# 04-ORIN_HIGH_SPEED_SIGNAL_2.net
KiCad netlist of a schematic drawn in Altium Designer
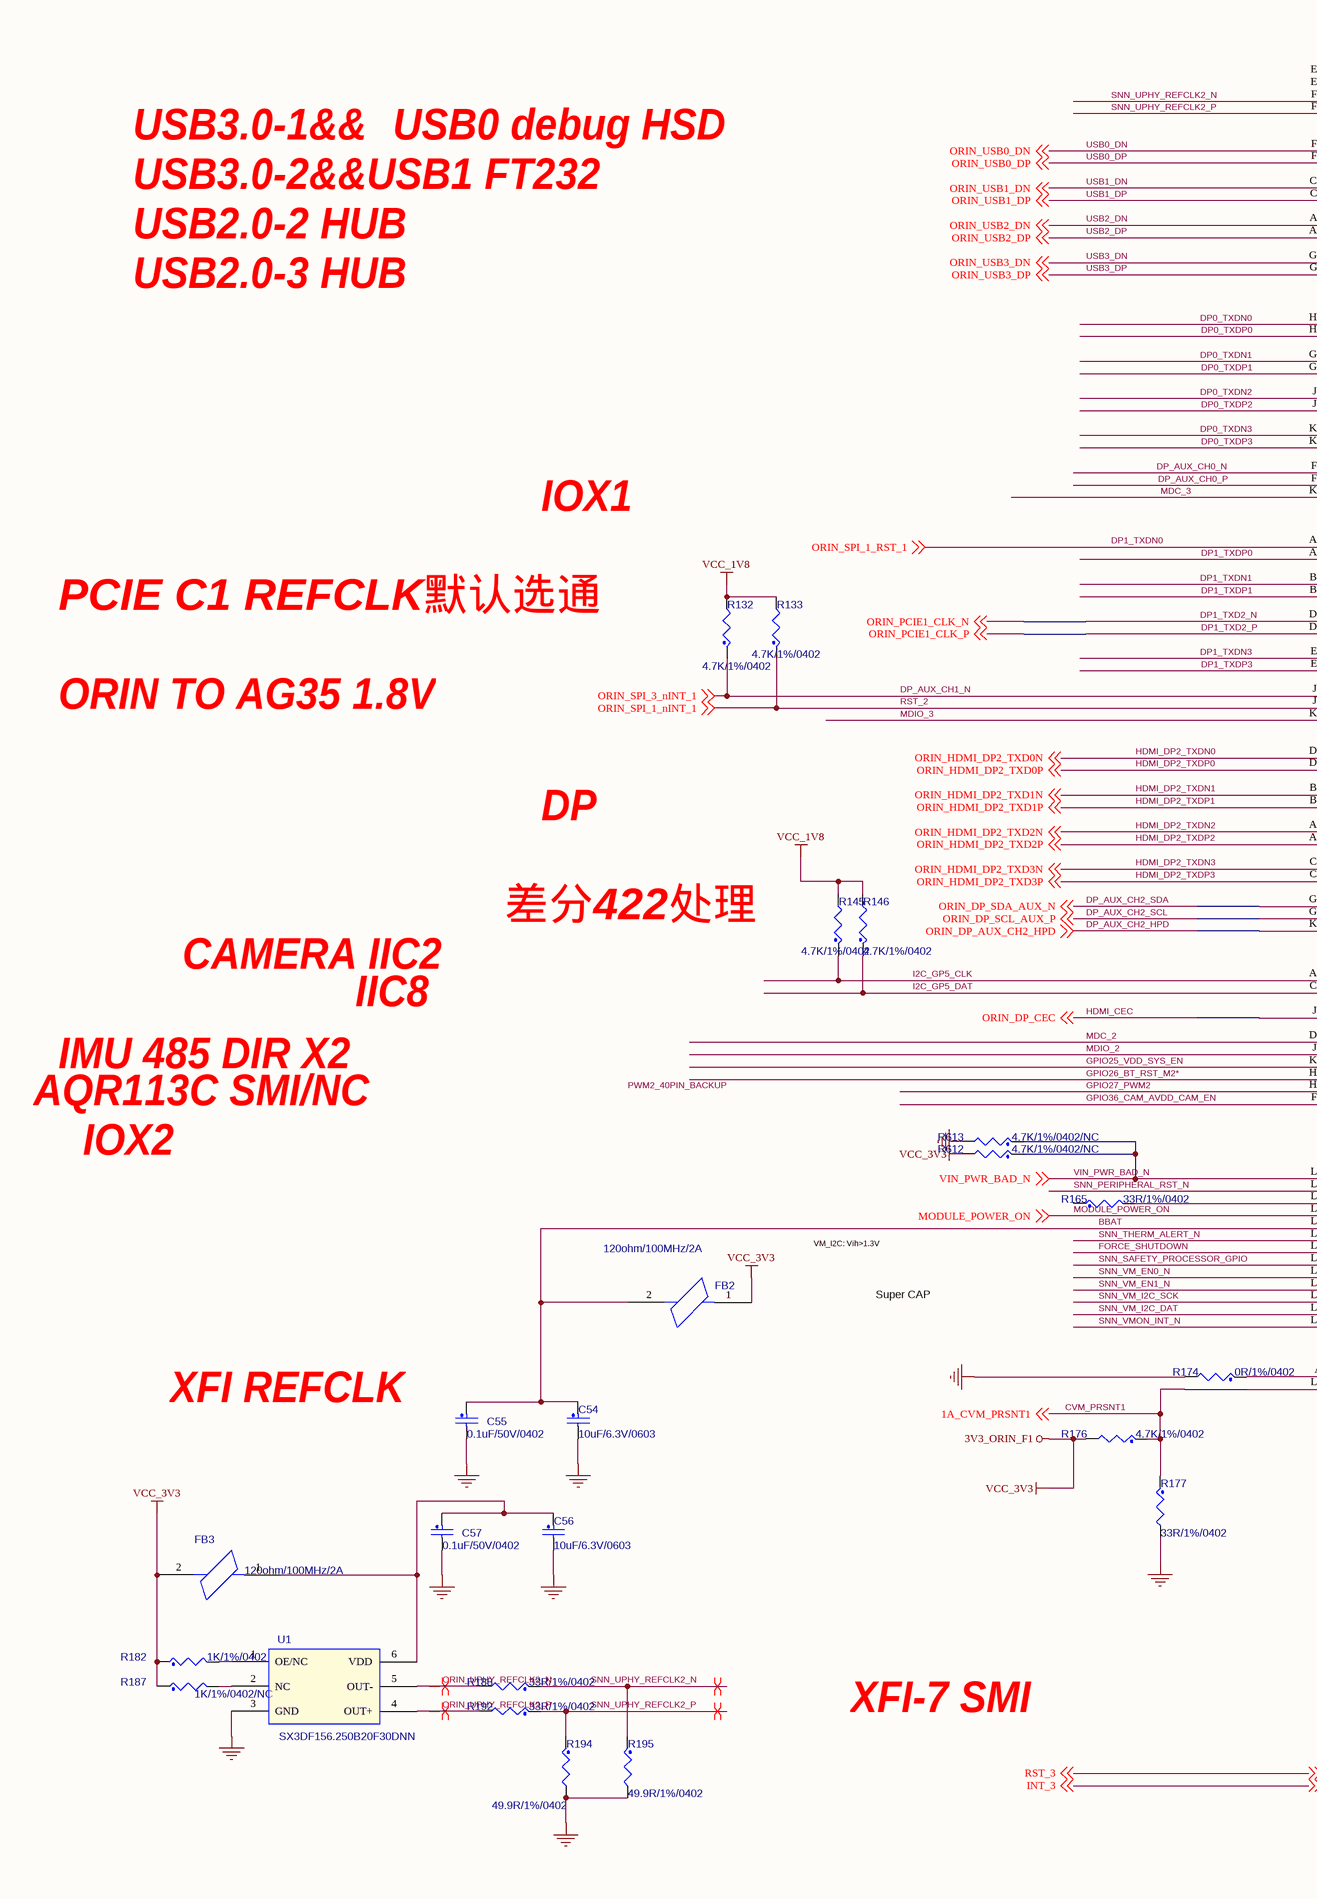
[diagram p0: 04-ORIN_HIGH_SPEED_SIGNAL_2.SchDoc, left]
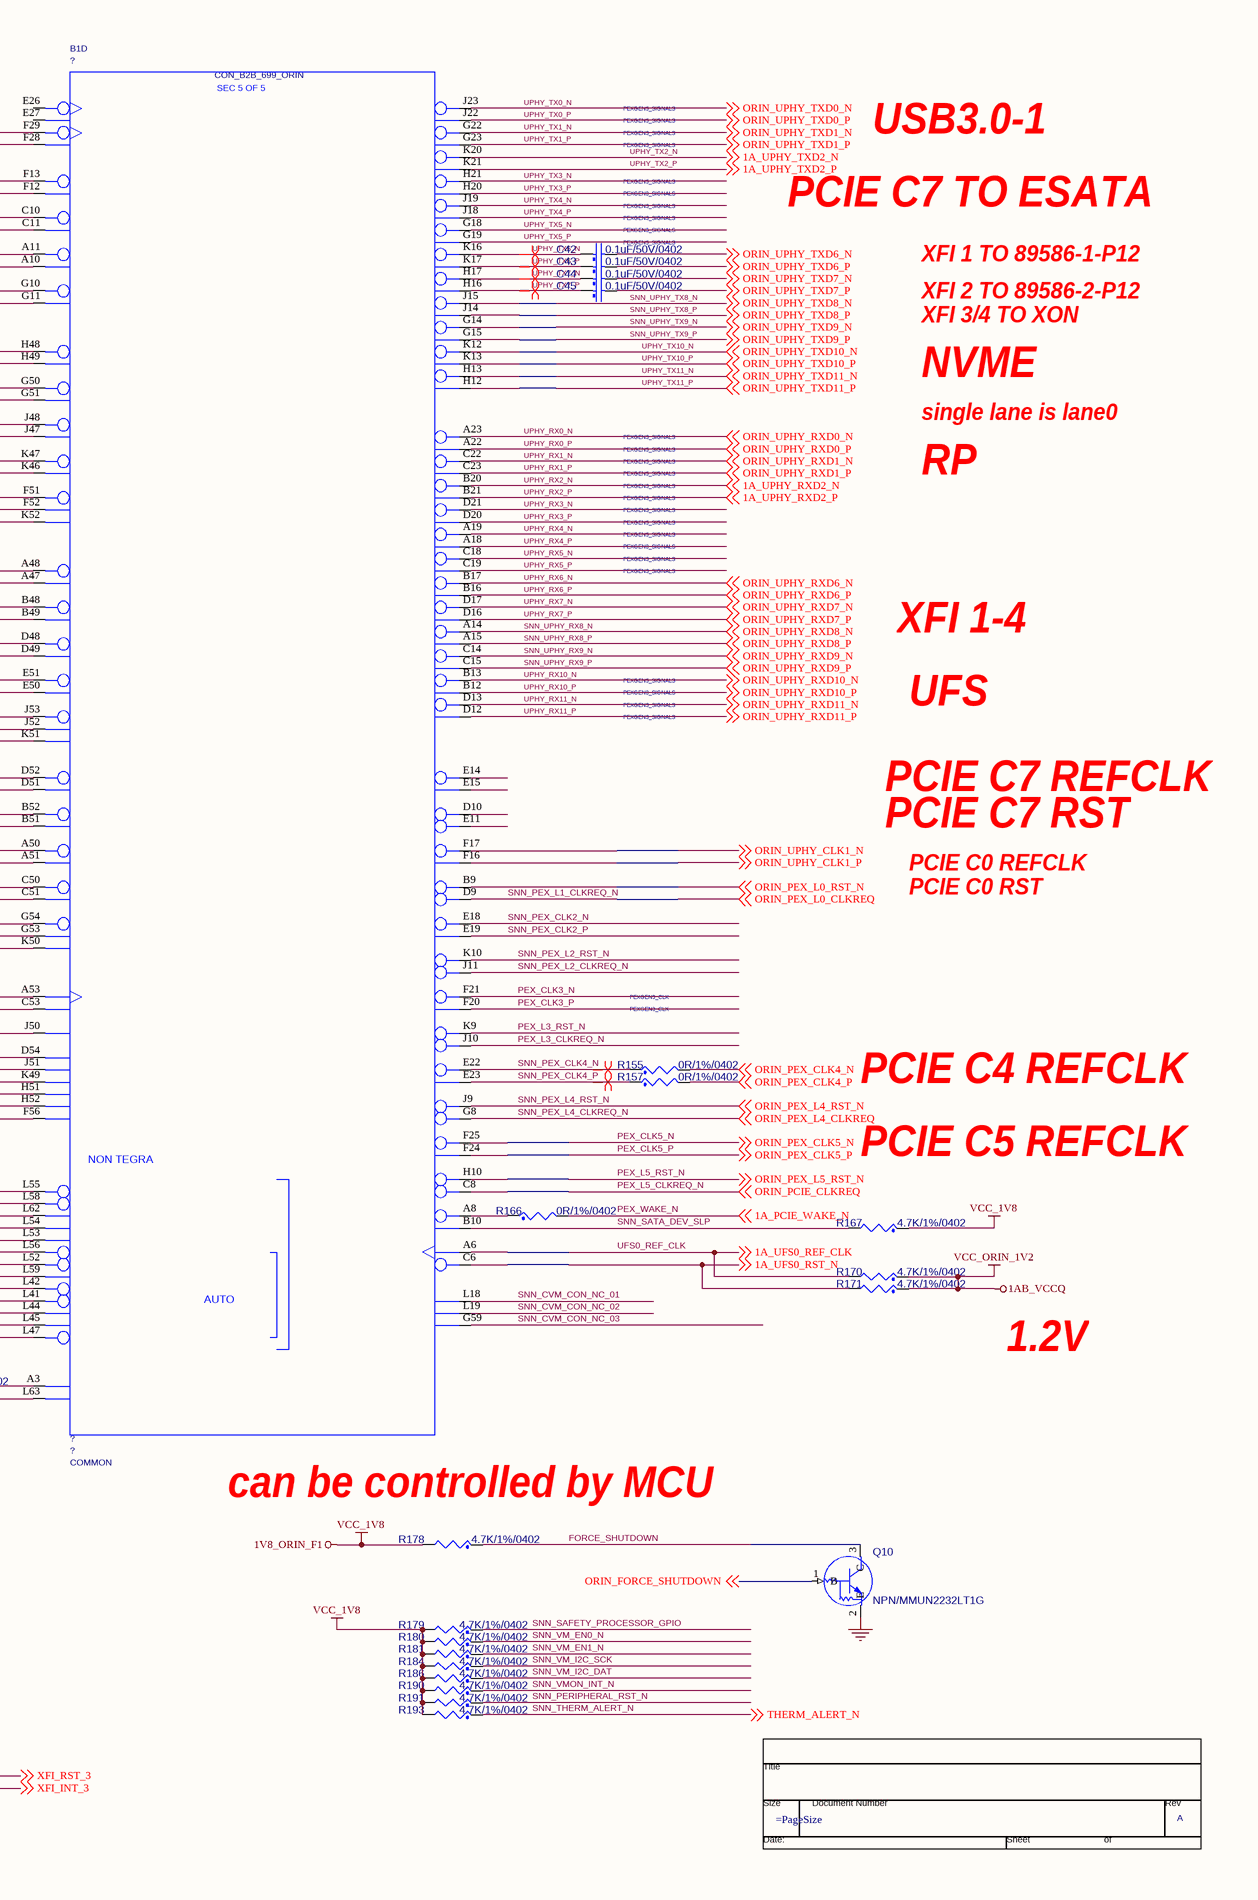
[diagram p1: 04-ORIN_HIGH_SPEED_SIGNAL_2.SchDoc, right]

(export (version "E")
  (design (tool "Eeschema 10.0.6"))
  (components
    (comp (ref "B1")
      (value "CON_B2B_699_ORIN")
      (footprint "CON_MIRMEZ_699_BGA_ST_P009_P013_P015_REVERSE")
      (description "2034560003/MOLEX")
      (fields
        (field (name "DEVICE") "CON_B2B_699_ORIN")
        (field (name "NV_PN") "?")
        (field (name "PACK_TYPE") "?")
        (field (name "PATH") "?")
        (field (name "SKU") "COMMON")
      )
      (libsource (lib "*") (part "CON_B2B_699"))
    )
    (comp (ref "C42")
      (value "0.1uF/50V/0402")
      (footprint "C0402")
      (description "GCM155R71H104KE02/MURATA")
      (fields (field (name "TOLERANCE") "10%") (field (name "VOLTAGE") "16V"))
      (libsource (lib "*") (part "CAP_NP"))
    )
    (comp (ref "C43")
      (value "0.1uF/50V/0402")
      (footprint "C0402")
      (description "GCM155R71H104KE02/MURATA")
      (fields (field (name "TOLERANCE") "10%") (field (name "VOLTAGE") "16V"))
      (libsource (lib "*") (part "CAP_NP"))
    )
    (comp (ref "C44")
      (value "0.1uF/50V/0402")
      (footprint "C0402")
      (description "GCM155R71H104KE02/MURATA")
      (fields (field (name "TOLERANCE") "10%") (field (name "VOLTAGE") "16V"))
      (libsource (lib "*") (part "CAP_NP"))
    )
    (comp (ref "C45")
      (value "0.1uF/50V/0402")
      (footprint "C0402")
      (description "GCM155R71H104KE02/MURATA")
      (fields (field (name "TOLERANCE") "10%") (field (name "VOLTAGE") "16V"))
      (libsource (lib "*") (part "CAP_NP"))
    )
    (comp (ref "C54")
      (value "10uF/6.3V/0603")
      (footprint "C0603")
      (description "GCM188D70J106ME36/MURATA")
      (fields (field (name "VOLTAGE") "10v") (field (name "TOLERANCE") "10%"))
      (libsource (lib "*") (part "CAP_NP"))
    )
    (comp (ref "C55")
      (value "0.1uF/50V/0402")
      (footprint "C0402")
      (description "GCM155R71H104KE02/MURATA")
      (fields (field (name "TOLERANCE") "10%") (field (name "VOLTAGE") "16V"))
      (libsource (lib "*") (part "CAP_NP"))
    )
    (comp (ref "C56")
      (value "10uF/6.3V/0603")
      (footprint "C0603")
      (description "GCM188D70J106ME36/MURATA")
      (fields (field (name "VOLTAGE") "10v") (field (name "TOLERANCE") "10%"))
      (libsource (lib "*") (part "CAP_NP"))
    )
    (comp (ref "C57")
      (value "0.1uF/50V/0402")
      (footprint "C0402")
      (description "GCM155R71H104KE02/MURATA")
      (fields (field (name "TOLERANCE") "10%") (field (name "VOLTAGE") "16V"))
      (libsource (lib "*") (part "CAP_NP"))
    )
    (comp (ref "FB2")
      (value "120ohm/100MHz/2A")
      (footprint "L0603")
      (description "BLM18EG121SH1D/MURATA")
      (fields (field (name "Comment") "BEAD_FERRITE"))
      (libsource (lib "*") (part "BEAD_FERRITE"))
    )
    (comp (ref "FB3")
      (value "120ohm/100MHz/2A")
      (footprint "L0603")
      (description "BLM18EG121SH1D/MURATA")
      (fields (field (name "Comment") "BEAD_FERRITE"))
      (libsource (lib "*") (part "BEAD_FERRITE"))
    )
    (comp (ref "Q10")
      (value "NPN/MMUN2232LT1G")
      (footprint "SOT-23")
      (description "MMUN2232LT1G/ONSEMI")
      (libsource (lib "*") (part "DTC143ZE"))
    )
    (comp (ref "R132")
      (value "4.7K/1%/0402")
      (footprint "R0402")
      (description "AC0402FR-074K7L/YAGEO")
      (fields (field (name "TOLERANCE") "5%") (field (name "Comment") "RES_Dup2"))
      (libsource (lib "*") (part "RES_Dup2"))
    )
    (comp (ref "R133")
      (value "4.7K/1%/0402")
      (footprint "R0402")
      (description "AC0402FR-074K7L/YAGEO")
      (fields (field (name "TOLERANCE") "5%") (field (name "Comment") "RES_Dup2"))
      (libsource (lib "*") (part "RES_Dup2"))
    )
    (comp (ref "R145")
      (value "4.7K/1%/0402")
      (footprint "R0402")
      (description "AC0402FR-074K7L/YAGEO")
      (fields (field (name "TOLERANCE") "5%") (field (name "Comment") "RES_Dup2"))
      (libsource (lib "*") (part "RES_Dup2"))
    )
    (comp (ref "R146")
      (value "4.7K/1%/0402")
      (footprint "R0402")
      (description "AC0402FR-074K7L/YAGEO")
      (fields (field (name "TOLERANCE") "5%") (field (name "Comment") "RES_Dup2"))
      (libsource (lib "*") (part "RES_Dup2"))
    )
    (comp (ref "R155")
      (value "0R/1%/0402")
      (footprint "R0402")
      (description "AC0402FR-070RL/YAGEO")
      (fields (field (name "TOLERANCE") "1%") (field (name "Comment") "RES_Dup2"))
      (libsource (lib "*") (part "RES_Dup2"))
    )
    (comp (ref "R157")
      (value "0R/1%/0402")
      (footprint "R0402")
      (description "AC0402FR-070RL/YAGEO")
      (fields (field (name "TOLERANCE") "1%") (field (name "Comment") "RES_Dup2"))
      (libsource (lib "*") (part "RES_Dup2"))
    )
    (comp (ref "R165")
      (value "33R/1%/0402")
      (footprint "R0402")
      (description "AC0402FR-0733RL/YAGEO")
      (fields (field (name "TOLERANCE") "1%") (field (name "Comment") "RES_Dup2"))
      (libsource (lib "*") (part "RES_Dup2"))
    )
    (comp (ref "R166")
      (value "0R/1%/0402")
      (footprint "R0402")
      (description "AC0402FR-070RL/YAGEO")
      (fields (field (name "TOLERANCE") "1%") (field (name "Comment") "RES_Dup2"))
      (libsource (lib "*") (part "RES_Dup2"))
    )
    (comp (ref "R167")
      (value "4.7K/1%/0402")
      (footprint "R0402")
      (description "AC0402FR-074K7L/YAGEO")
      (fields (field (name "TOLERANCE") "5%") (field (name "Comment") "RES_Dup2"))
      (libsource (lib "*") (part "RES_Dup2"))
    )
    (comp (ref "R170")
      (value "4.7K/1%/0402")
      (footprint "R0402")
      (description "AC0402FR-074K7L/YAGEO")
      (fields (field (name "TOLERANCE") "5%") (field (name "Comment") "RES_Dup2"))
      (libsource (lib "*") (part "RES_Dup2"))
    )
    (comp (ref "R171")
      (value "4.7K/1%/0402")
      (footprint "R0402")
      (description "AC0402FR-074K7L/YAGEO")
      (fields (field (name "TOLERANCE") "5%") (field (name "Comment") "RES_Dup2"))
      (libsource (lib "*") (part "RES_Dup2"))
    )
    (comp (ref "R174")
      (value "0R/1%/0402")
      (footprint "R0402")
      (description "AC0402FR-070RL/YAGEO")
      (fields (field (name "TOLERANCE") "5%") (field (name "Comment") "RES_Dup2"))
      (libsource (lib "*") (part "RES_Dup2"))
    )
    (comp (ref "R176")
      (value "4.7K/1%/0402")
      (footprint "R0402")
      (description "AC0402FR-074K7L/YAGEO")
      (fields (field (name "TOLERANCE") "5%") (field (name "Comment") "RES_Dup2"))
      (libsource (lib "*") (part "RES_Dup2"))
    )
    (comp (ref "R177")
      (value "33R/1%/0402")
      (footprint "R0402")
      (description "AC0402FR-0733RL/YAGEO")
      (fields (field (name "TOLERANCE") "5%") (field (name "Comment") "RES_Dup2"))
      (libsource (lib "*") (part "RES_Dup2"))
    )
    (comp (ref "R178")
      (value "4.7K/1%/0402")
      (footprint "R0402")
      (description "AC0402FR-074K7L/YAGEO")
      (fields (field (name "TOLERANCE") "5%") (field (name "Comment") "RES_Dup2"))
      (libsource (lib "*") (part "RES_Dup2"))
    )
    (comp (ref "R179")
      (value "4.7K/1%/0402")
      (footprint "R0402")
      (description "AC0402FR-074K7L/YAGEO")
      (fields (field (name "TOLERANCE") "5%") (field (name "Comment") "RES_Dup2"))
      (libsource (lib "*") (part "RES_Dup2"))
    )
    (comp (ref "R180")
      (value "4.7K/1%/0402")
      (footprint "R0402")
      (description "AC0402FR-074K7L/YAGEO")
      (fields (field (name "TOLERANCE") "5%") (field (name "Comment") "RES_Dup2"))
      (libsource (lib "*") (part "RES_Dup2"))
    )
    (comp (ref "R181")
      (value "4.7K/1%/0402")
      (footprint "R0402")
      (description "AC0402FR-074K7L/YAGEO")
      (fields (field (name "TOLERANCE") "5%") (field (name "Comment") "RES_Dup2"))
      (libsource (lib "*") (part "RES_Dup2"))
    )
    (comp (ref "R182")
      (value "1K/1%/0402")
      (footprint "R0402")
      (description "AC0402FR-071KL/YAGEO")
      (fields (field (name "TOLERANCE") "5%") (field (name "Comment") "RES_Dup2"))
      (libsource (lib "*") (part "RES_Dup2"))
    )
    (comp (ref "R184")
      (value "4.7K/1%/0402")
      (footprint "R0402")
      (description "AC0402FR-074K7L/YAGEO")
      (fields (field (name "TOLERANCE") "5%") (field (name "Comment") "RES_Dup2"))
      (libsource (lib "*") (part "RES_Dup2"))
    )
    (comp (ref "R186")
      (value "4.7K/1%/0402")
      (footprint "R0402")
      (description "AC0402FR-074K7L/YAGEO")
      (fields (field (name "TOLERANCE") "5%") (field (name "Comment") "RES_Dup2"))
      (libsource (lib "*") (part "RES_Dup2"))
    )
    (comp (ref "R187")
      (value "1K/1%/0402/NC")
      (footprint "R0402")
      (description "AC0402FR-071KL/YAGEO")
      (fields (field (name "TOLERANCE") "5%") (field (name "Comment") "RES_Dup2"))
      (libsource (lib "*") (part "RES_Dup2"))
    )
    (comp (ref "R188")
      (value "33R/1%/0402")
      (footprint "R0402")
      (description "AC0402FR-0733RL/YAGEO")
      (fields (field (name "TOLERANCE") "5%") (field (name "Comment") "RES_Dup2"))
      (libsource (lib "*") (part "RES_Dup2"))
    )
    (comp (ref "R190")
      (value "4.7K/1%/0402")
      (footprint "R0402")
      (description "AC0402FR-074K7L/YAGEO")
      (fields (field (name "TOLERANCE") "5%") (field (name "Comment") "RES_Dup2"))
      (libsource (lib "*") (part "RES_Dup2"))
    )
    (comp (ref "R191")
      (value "4.7K/1%/0402")
      (footprint "R0402")
      (description "AC0402FR-074K7L/YAGEO")
      (fields (field (name "TOLERANCE") "5%") (field (name "Comment") "RES_Dup2"))
      (libsource (lib "*") (part "RES_Dup2"))
    )
    (comp (ref "R192")
      (value "33R/1%/0402")
      (footprint "R0402")
      (description "AC0402FR-0733RL/YAGEO")
      (fields (field (name "TOLERANCE") "5%") (field (name "Comment") "RES_Dup2"))
      (libsource (lib "*") (part "RES_Dup2"))
    )
    (comp (ref "R193")
      (value "4.7K/1%/0402")
      (footprint "R0402")
      (description "AC0402FR-074K7L/YAGEO")
      (fields (field (name "TOLERANCE") "5%") (field (name "Comment") "RES_Dup2"))
      (libsource (lib "*") (part "RES_Dup2"))
    )
    (comp (ref "R194")
      (value "49.9R/1%/0402")
      (footprint "R0402")
      (description "AC0402FR-0749R9L/YAGEO")
      (fields (field (name "TOLERANCE") "5%") (field (name "Comment") "RES_Dup2"))
      (libsource (lib "*") (part "RES_Dup2"))
    )
    (comp (ref "R195")
      (value "49.9R/1%/0402")
      (footprint "R0402")
      (description "AC0402FR-0749R9L/YAGEO")
      (fields (field (name "TOLERANCE") "5%") (field (name "Comment") "RES_Dup2"))
      (libsource (lib "*") (part "RES_Dup2"))
    )
    (comp (ref "R612")
      (value "4.7K/1%/0402/NC")
      (footprint "R0402")
      (description "AC0402FR-074K7L/YAGEO")
      (fields (field (name "TOLERANCE") "5%") (field (name "Comment") "RES_Dup2"))
      (libsource (lib "*") (part "RES_Dup2"))
    )
    (comp (ref "R613")
      (value "4.7K/1%/0402/NC")
      (footprint "R0402")
      (description "AC0402FR-074K7L/YAGEO")
      (fields (field (name "TOLERANCE") "5%") (field (name "Comment") "RES_Dup2"))
      (libsource (lib "*") (part "RES_Dup2"))
    )
    (comp (ref "U1")
      (value "SX3DF156.250B20F30DNN")
      (footprint "SX3DF156.250B20F30DNN")
      (description "SiT9365AI-4B2-33E156.25MHZ/SITIME")
      (libsource (lib "*") (part "SiT9365AI-4B2-33E156.25MHZ"))
    )
  )
  (nets
    (net (code "1") (name "/BBAT") (class "Default")
      (node (ref "B1") (pin "L53") (pinfunction "VCC_RTC_L53") (pintype "bidirectional"))
      (node (ref "C54") (pin "1") (pinfunction "1_1") (pintype "passive"))
      (node (ref "C55") (pin "1") (pinfunction "1_1") (pintype "passive"))
      (node (ref "FB2") (pin "2") (pinfunction "2_2") (pintype "passive"))
    )
    (net (code "2") (name "/DP0_TXDN0") (class "Default")
      (node (ref "B1") (pin "H48") (pinfunction "HDMI_DP0_TX0_N_H48") (pintype "bidirectional"))
    )
    (net (code "3") (name "/DP0_TXDN1") (class "Default")
      (node (ref "B1") (pin "G50") (pinfunction "HDMI_DP0_TX1_N_G50") (pintype "bidirectional"))
    )
    (net (code "4") (name "/DP0_TXDN2") (class "Default")
      (node (ref "B1") (pin "J48") (pinfunction "HDMI_DP0_TX2_N_J48") (pintype "bidirectional"))
    )
    (net (code "5") (name "/DP0_TXDN3") (class "Default")
      (node (ref "B1") (pin "K47") (pinfunction "HDMI_DP0_TX3_N_K47") (pintype "bidirectional"))
    )
    (net (code "6") (name "/DP0_TXDP0") (class "Default")
      (node (ref "B1") (pin "H49") (pinfunction "HDMI_DP0_TX0_P_H49") (pintype "bidirectional"))
    )
    (net (code "7") (name "/DP0_TXDP1") (class "Default")
      (node (ref "B1") (pin "G51") (pinfunction "HDMI_DP0_TX1_P_G51") (pintype "bidirectional"))
    )
    (net (code "8") (name "/DP0_TXDP2") (class "Default")
      (node (ref "B1") (pin "J47") (pinfunction "HDMI_DP0_TX2_P_J47") (pintype "bidirectional"))
    )
    (net (code "9") (name "/DP0_TXDP3") (class "Default")
      (node (ref "B1") (pin "K46") (pinfunction "HDMI_DP0_TX3_P_K46") (pintype "bidirectional"))
    )
    (net (code "10") (name "/DP1_TXDN1") (class "Default")
      (node (ref "B1") (pin "B48") (pinfunction "HDMI_DP1_TX1_N_B48") (pintype "bidirectional"))
    )
    (net (code "11") (name "/DP1_TXDN3") (class "Default")
      (node (ref "B1") (pin "E51") (pinfunction "HDMI_DP1_TX3_N_E51") (pintype "bidirectional"))
    )
    (net (code "12") (name "/DP1_TXDP0") (class "Default")
      (node (ref "B1") (pin "A47") (pinfunction "HDMI_DP1_TX0_P_A47") (pintype "bidirectional"))
    )
    (net (code "13") (name "/DP1_TXDP1") (class "Default")
      (node (ref "B1") (pin "B49") (pinfunction "HDMI_DP1_TX1_P_B49") (pintype "bidirectional"))
    )
    (net (code "14") (name "/DP1_TXDP3") (class "Default")
      (node (ref "B1") (pin "E50") (pinfunction "HDMI_DP1_TX3_P_E50") (pintype "bidirectional"))
    )
    (net (code "15") (name "/DP_AUX_CH0_N") (class "Default")
      (node (ref "B1") (pin "F51") (pinfunction "DP0_AUX_CH_N_F51") (pintype "bidirectional"))
    )
    (net (code "16") (name "/DP_AUX_CH0_P") (class "Default")
      (node (ref "B1") (pin "F52") (pinfunction "DP0_AUX_CH_P_F52") (pintype "bidirectional"))
    )
    (net (code "17") (name "/FORCE_SHUTDOWN") (class "Default")
      (node (ref "B1") (pin "L52") (pinfunction "OVERTEMP_N_L52") (pintype "bidirectional"))
      (node (ref "Q10") (pin "3") (pinfunction "C_3") (pintype "passive"))
      (node (ref "R178") (pin "1") (pinfunction "1_1") (pintype "passive"))
    )
    (net (code "18") (name "/GPIO25_VDD_SYS_EN") (class "Default")
      (node (ref "B1") (pin "K49") (pinfunction "GPIO25_K49") (pintype "bidirectional"))
    )
    (net (code "19") (name "/GPIO26_BT_RST_M2*") (class "Default")
      (node (ref "B1") (pin "H51") (pinfunction "GPIO26_H51") (pintype "bidirectional"))
    )
    (net (code "20") (name "/GPIO27_PWM2") (class "Default")
      (node (ref "B1") (pin "H52") (pinfunction "GPIO27_H52") (pintype "bidirectional"))
    )
    (net (code "21") (name "/GPIO36_CAM_AVDD_CAM_EN") (class "Default")
      (node (ref "B1") (pin "F56") (pinfunction "GPIO36_F56") (pintype "bidirectional"))
    )
    (net (code "22") (name "/I2C_GP5_CLK") (class "Default")
      (node (ref "B1") (pin "A53") (pinfunction "I2C5_CLK_A53") (pintype "bidirectional"))
      (node (ref "R145") (pin "1") (pinfunction "1_1") (pintype "passive"))
    )
    (net (code "23") (name "/I2C_GP5_DAT") (class "Default")
      (node (ref "B1") (pin "C53") (pinfunction "I2C5_DAT_C53") (pintype "bidirectional"))
      (node (ref "R146") (pin "1") (pinfunction "1_1") (pintype "passive"))
    )
    (net (code "24") (name "/MDC_2") (class "Default")
      (node (ref "B1") (pin "D54") (pinfunction "GPIO03_D54") (pintype "bidirectional"))
    )
    (net (code "25") (name "/MDC_3") (class "Default")
      (node (ref "B1") (pin "K52") (pinfunction "DP0_HPD_K52") (pintype "bidirectional"))
    )
    (net (code "26") (name "/MDIO_2") (class "Default")
      (node (ref "B1") (pin "J51") (pinfunction "GPIO24_J51") (pintype "bidirectional"))
    )
    (net (code "27") (name "/MDIO_3") (class "Default")
      (node (ref "B1") (pin "K51") (pinfunction "DP1_HPD_K51") (pintype "bidirectional"))
    )
    (net (code "28") (name "/ORIN_UPHY_REFCLK2_N") (class "Default")
      (node (ref "R188") (pin "2") (pinfunction "2_2") (pintype "passive"))
      (node (ref "U1") (pin "5") (pinfunction "OUT-_5") (pintype "passive"))
    )
    (net (code "29") (name "/ORIN_UPHY_REFCLK2_P") (class "Default")
      (node (ref "R192") (pin "2") (pinfunction "2_2") (pintype "passive"))
      (node (ref "U1") (pin "4") (pinfunction "OUT+_4") (pintype "passive"))
    )
    (net (code "30") (name "/PEX_CLK3_N") (class "Default")
      (node (ref "B1") (pin "F21") (pinfunction "PEX_CLK3_N_F21") (pintype "bidirectional"))
    )
    (net (code "31") (name "/PEX_CLK3_P") (class "Default")
      (node (ref "B1") (pin "F20") (pinfunction "PEX_CLK3_P_F20") (pintype "bidirectional"))
    )
    (net (code "32") (name "/PEX_L3_CLKREQ_N") (class "Default")
      (node (ref "B1") (pin "J10") (pinfunction "PEX_C3_CLKREQ_N_J10") (pintype "bidirectional"))
    )
    (net (code "33") (name "/PEX_L3_RST_N") (class "Default")
      (node (ref "B1") (pin "K9") (pinfunction "PEX_C3_RST_N_K9") (pintype "bidirectional"))
    )
    (net (code "35") (name "/SNN_CVM_CON_NC_01") (class "Default")
      (node (ref "B1") (pin "L18") (pinfunction "NC_01_L18") (pintype "bidirectional"))
    )
    (net (code "36") (name "/SNN_CVM_CON_NC_02") (class "Default")
      (node (ref "B1") (pin "L19") (pinfunction "NC_02_L19") (pintype "bidirectional"))
    )
    (net (code "37") (name "/SNN_CVM_CON_NC_03") (class "Default")
      (node (ref "B1") (pin "G59") (pinfunction "NC_03_G59") (pintype "bidirectional"))
    )
    (net (code "38") (name "/SNN_PERIPHERAL_RST_N") (class "Default")
      (node (ref "B1") (pin "L58") (pinfunction "PERIPHERAL_RESET_N_L58") (pintype "bidirectional"))
      (node (ref "R191") (pin "1") (pinfunction "1_1") (pintype "passive"))
    )
    (net (code "39") (name "/SNN_PEX_CLK2_N") (class "Default")
      (node (ref "B1") (pin "E18") (pinfunction "PEX_CLK2_N_E18") (pintype "bidirectional"))
    )
    (net (code "40") (name "/SNN_PEX_CLK2_P") (class "Default")
      (node (ref "B1") (pin "E19") (pinfunction "PEX_CLK2_P_E19") (pintype "bidirectional"))
    )
    (net (code "41") (name "/SNN_PEX_CLK4_N") (class "Default")
      (node (ref "B1") (pin "E22") (pinfunction "PEX_CLK4_N_E22") (pintype "bidirectional"))
      (node (ref "R155") (pin "1") (pinfunction "1_1") (pintype "passive"))
    )
    (net (code "42") (name "/SNN_PEX_CLK4_P") (class "Default")
      (node (ref "B1") (pin "E23") (pinfunction "PEX_CLK4_P_E23") (pintype "bidirectional"))
      (node (ref "R157") (pin "1") (pinfunction "1_1") (pintype "passive"))
    )
    (net (code "43") (name "/SNN_PEX_L2_CLKREQ_N") (class "Default")
      (node (ref "B1") (pin "J11") (pinfunction "PEX_C2_CLKREQ_N_J11") (pintype "bidirectional"))
    )
    (net (code "44") (name "/SNN_PEX_L2_RST_N") (class "Default")
      (node (ref "B1") (pin "K10") (pinfunction "PEX_C2_RST_N_K10") (pintype "bidirectional"))
    )
    (net (code "45") (name "/SNN_SAFETY_PROCESSOR_GPIO") (class "Default")
      (node (ref "B1") (pin "L59") (pinfunction "SAFETY_PROCESSOR_GPIO_L59") (pintype "bidirectional"))
      (node (ref "R179") (pin "1") (pinfunction "1_1") (pintype "passive"))
    )
    (net (code "46") (name "/SNN_SATA_DEV_SLP") (class "Default")
      (node (ref "B1") (pin "B10") (pinfunction "SATA_DEV_SLP_B10") (pintype "bidirectional"))
      (node (ref "R167") (pin "2") (pinfunction "2_2") (pintype "passive"))
    )
    (net (code "47") (name "/SNN_UPHY_REFCLK2_N") (class "Default")
      (node (ref "B1") (pin "F29") (pinfunction "UPHY_REFCLK2_N_F29") (pintype "bidirectional"))
      (node (ref "R188") (pin "1") (pinfunction "1_1") (pintype "passive"))
      (node (ref "R195") (pin "1") (pinfunction "1_1") (pintype "passive"))
    )
    (net (code "48") (name "/SNN_UPHY_REFCLK2_P") (class "Default")
      (node (ref "B1") (pin "F28") (pinfunction "UPHY_REFCLK2_P_F28") (pintype "bidirectional"))
      (node (ref "R192") (pin "1") (pinfunction "1_1") (pintype "passive"))
      (node (ref "R194") (pin "1") (pinfunction "1_1") (pintype "passive"))
    )
    (net (code "49") (name "/SNN_VMON_INT_N") (class "Default")
      (node (ref "B1") (pin "L47") (pinfunction "VM_INT_N_L47") (pintype "bidirectional"))
      (node (ref "R190") (pin "1") (pinfunction "1_1") (pintype "passive"))
    )
    (net (code "50") (name "/SNN_VM_EN0_N") (class "Default")
      (node (ref "B1") (pin "L42") (pinfunction "VM_EN0_N_L42") (pintype "bidirectional"))
      (node (ref "R180") (pin "1") (pinfunction "1_1") (pintype "passive"))
    )
    (net (code "51") (name "/SNN_VM_EN1_N") (class "Default")
      (node (ref "B1") (pin "L41") (pinfunction "VM_EN1_N_L41") (pintype "bidirectional"))
      (node (ref "R181") (pin "1") (pinfunction "1_1") (pintype "passive"))
    )
    (net (code "52") (name "/SNN_VM_I2C_DAT") (class "Default")
      (node (ref "B1") (pin "L45") (pinfunction "VM_I2C_DAT_L45") (pintype "bidirectional"))
      (node (ref "R186") (pin "1") (pinfunction "1_1") (pintype "passive"))
    )
    (net (code "53") (name "/SNN_VM_I2C_SCK") (class "Default")
      (node (ref "B1") (pin "L44") (pinfunction "VM_I2C_SCK_L44") (pintype "bidirectional"))
      (node (ref "R184") (pin "1") (pinfunction "1_1") (pintype "passive"))
    )
    (net (code "54") (name "/UPHY_RX3_N") (class "Default")
      (node (ref "B1") (pin "D21") (pinfunction "UPHY_RX3_N_D21") (pintype "bidirectional"))
    )
    (net (code "55") (name "/UPHY_RX3_P") (class "Default")
      (node (ref "B1") (pin "D20") (pinfunction "UPHY_RX3_P_D20") (pintype "bidirectional"))
    )
    (net (code "56") (name "/UPHY_RX4_N") (class "Default")
      (node (ref "B1") (pin "A19") (pinfunction "UPHY_RX4_N_A19") (pintype "bidirectional"))
    )
    (net (code "57") (name "/UPHY_RX4_P") (class "Default")
      (node (ref "B1") (pin "A18") (pinfunction "UPHY_RX4_P_A18") (pintype "bidirectional"))
    )
    (net (code "58") (name "/UPHY_RX5_N") (class "Default")
      (node (ref "B1") (pin "C18") (pinfunction "UPHY_RX5_N_C18") (pintype "bidirectional"))
    )
    (net (code "59") (name "/UPHY_RX5_P") (class "Default")
      (node (ref "B1") (pin "C19") (pinfunction "UPHY_RX5_P_C19") (pintype "bidirectional"))
    )
    (net (code "60") (name "/UPHY_TX3_N") (class "Default")
      (node (ref "B1") (pin "H21") (pinfunction "UPHY_TX3_N_H21") (pintype "bidirectional"))
    )
    (net (code "61") (name "/UPHY_TX3_P") (class "Default")
      (node (ref "B1") (pin "H20") (pinfunction "UPHY_TX3_P_H20") (pintype "bidirectional"))
    )
    (net (code "62") (name "/UPHY_TX4_N") (class "Default")
      (node (ref "B1") (pin "J19") (pinfunction "UPHY_TX4_N_J19") (pintype "bidirectional"))
    )
    (net (code "63") (name "/UPHY_TX4_P") (class "Default")
      (node (ref "B1") (pin "J18") (pinfunction "UPHY_TX4_P_J18") (pintype "bidirectional"))
    )
    (net (code "64") (name "/UPHY_TX5_N") (class "Default")
      (node (ref "B1") (pin "G18") (pinfunction "UPHY_TX5_N_G18") (pintype "bidirectional"))
    )
    (net (code "65") (name "/UPHY_TX5_P") (class "Default")
      (node (ref "B1") (pin "G19") (pinfunction "UPHY_TX5_P_G19") (pintype "bidirectional"))
    )
    (net (code "66") (name "/UPHY_TX6_N") (class "Default")
      (node (ref "B1") (pin "K16") (pinfunction "UPHY_TX6_N_K16") (pintype "bidirectional"))
      (node (ref "C42") (pin "1") (pinfunction "1_1") (pintype "passive"))
    )
    (net (code "67") (name "/UPHY_TX6_P") (class "Default")
      (node (ref "B1") (pin "K17") (pinfunction "UPHY_TX6_P_K17") (pintype "bidirectional"))
      (node (ref "C43") (pin "1") (pinfunction "1_1") (pintype "passive"))
    )
    (net (code "68") (name "/UPHY_TX7_N") (class "Default")
      (node (ref "B1") (pin "H17") (pinfunction "UPHY_TX7_N_H17") (pintype "bidirectional"))
      (node (ref "C44") (pin "1") (pinfunction "1_1") (pintype "passive"))
    )
    (net (code "69") (name "/UPHY_TX7_P") (class "Default")
      (node (ref "B1") (pin "H16") (pinfunction "UPHY_TX7_P_H16") (pintype "bidirectional"))
      (node (ref "C45") (pin "1") (pinfunction "1_1") (pintype "passive"))
    )
    (net (code "70") (name "1AB_VCCQ") (class "Default")
      (node (ref "R170") (pin "1") (pinfunction "1_1") (pintype "passive"))
      (node (ref "R171") (pin "1") (pinfunction "1_1") (pintype "passive"))
    )
    (net (code "71") (name "1A_CVM_PRSNT1") (class "Default")
      (node (ref "B1") (pin "L63") (pinfunction "PRSNT1_L63") (pintype "bidirectional"))
      (node (ref "R176") (pin "1") (pinfunction "1_1") (pintype "passive"))
      (node (ref "R177") (pin "1") (pinfunction "1_1") (pintype "passive"))
    )
    (net (code "72") (name "1A_PCIE_WAKE_N") (class "Default")
      (node (ref "R166") (pin "2") (pinfunction "2_2") (pintype "passive"))
    )
    (net (code "73") (name "1A_UFS0_REF_CLK") (class "Default")
      (node (ref "B1") (pin "A6") (pinfunction "UFS0_REF_CLK_A6") (pintype "bidirectional"))
      (node (ref "R170") (pin "2") (pinfunction "2_2") (pintype "passive"))
    )
    (net (code "74") (name "1A_UFS0_RST_N") (class "Default")
      (node (ref "B1") (pin "C6") (pinfunction "UFS0_RST_N_C6") (pintype "bidirectional"))
      (node (ref "R171") (pin "2") (pinfunction "2_2") (pintype "passive"))
    )
    (net (code "75") (name "1A_UPHY_RXD2_N") (class "Default")
      (node (ref "B1") (pin "B20") (pinfunction "UPHY_RX2_N_B20") (pintype "bidirectional"))
    )
    (net (code "76") (name "1A_UPHY_RXD2_P") (class "Default")
      (node (ref "B1") (pin "B21") (pinfunction "UPHY_RX2_P_B21") (pintype "bidirectional"))
    )
    (net (code "77") (name "1A_UPHY_TXD2_N") (class "Default")
      (node (ref "B1") (pin "K20") (pinfunction "UPHY_TX2_N_K20") (pintype "bidirectional"))
    )
    (net (code "78") (name "1A_UPHY_TXD2_P") (class "Default")
      (node (ref "B1") (pin "K21") (pinfunction "UPHY_TX2_P_K21") (pintype "bidirectional"))
    )
    (net (code "79") (name "1V8_ORIN_F1") (class "Default")
      (node (ref "R132") (pin "2") (pinfunction "2_2") (pintype "passive"))
      (node (ref "R133") (pin "2") (pinfunction "2_2") (pintype "passive"))
      (node (ref "R145") (pin "2") (pinfunction "2_2") (pintype "passive"))
      (node (ref "R146") (pin "2") (pinfunction "2_2") (pintype "passive"))
      (node (ref "R167") (pin "1") (pinfunction "1_1") (pintype "passive"))
      (node (ref "R178") (pin "2") (pinfunction "2_2") (pintype "passive"))
      (node (ref "R179") (pin "2") (pinfunction "2_2") (pintype "passive"))
      (node (ref "R180") (pin "2") (pinfunction "2_2") (pintype "passive"))
      (node (ref "R181") (pin "2") (pinfunction "2_2") (pintype "passive"))
      (node (ref "R184") (pin "2") (pinfunction "2_2") (pintype "passive"))
      (node (ref "R186") (pin "2") (pinfunction "2_2") (pintype "passive"))
      (node (ref "R190") (pin "2") (pinfunction "2_2") (pintype "passive"))
      (node (ref "R191") (pin "2") (pinfunction "2_2") (pintype "passive"))
      (node (ref "R193") (pin "2") (pinfunction "2_2") (pintype "passive"))
    )
    (net (code "80") (name "3V3_ORIN_F1") (class "Default")
      (node (ref "FB2") (pin "1") (pinfunction "1_1") (pintype "passive"))
      (node (ref "FB3") (pin "2") (pinfunction "2_2") (pintype "passive"))
      (node (ref "R176") (pin "2") (pinfunction "2_2") (pintype "passive"))
      (node (ref "R182") (pin "1") (pinfunction "1_1") (pintype "passive"))
      (node (ref "R187") (pin "1") (pinfunction "1_1") (pintype "passive"))
      (node (ref "R612") (pin "2") (pinfunction "2_2") (pintype "passive"))
    )
    (net (code "81") (name "GND") (class "Default")
      (node (ref "C54") (pin "2") (pinfunction "2_2") (pintype "passive"))
      (node (ref "C55") (pin "2") (pinfunction "2_2") (pintype "passive"))
      (node (ref "C56") (pin "2") (pinfunction "2_2") (pintype "passive"))
      (node (ref "C57") (pin "2") (pinfunction "2_2") (pintype "passive"))
      (node (ref "Q10") (pin "2") (pinfunction "E_2") (pintype "passive"))
      (node (ref "R174") (pin "2") (pinfunction "2_2") (pintype "passive"))
      (node (ref "R177") (pin "2") (pinfunction "2_2") (pintype "passive"))
      (node (ref "R194") (pin "2") (pinfunction "2_2") (pintype "passive"))
      (node (ref "R195") (pin "2") (pinfunction "2_2") (pintype "passive"))
      (node (ref "R613") (pin "2") (pinfunction "2_2") (pintype "passive"))
      (node (ref "U1") (pin "3") (pinfunction "GND_3") (pintype "passive"))
    )
    (net (code "83") (name "MODULE_POWER_ON") (class "Default")
      (node (ref "B1") (pin "L54") (pinfunction "MODULE_POWER_ON_L54") (pintype "bidirectional"))
    )
    (net (code "84") (name "Net-(B1D-CARRIER_POWER_ON)") (class "Default")
      (node (ref "B1") (pin "L62") (pinfunction "CARRIER_POWER_ON_L62") (pintype "bidirectional"))
      (node (ref "R165") (pin "2") (pinfunction "2_2") (pintype "passive"))
    )
    (net (code "85") (name "Net-(B1D-PEX_WAKE_N)") (class "Default")
      (node (ref "B1") (pin "A8") (pinfunction "PEX_WAKE_N_A8") (pintype "bidirectional"))
      (node (ref "R166") (pin "1") (pinfunction "1_1") (pintype "passive"))
    )
    (net (code "86") (name "Net-(B1D-PRSNT0)") (class "Default")
      (node (ref "B1") (pin "A3") (pinfunction "PRSNT0_A3") (pintype "bidirectional"))
      (node (ref "R174") (pin "1") (pinfunction "1_1") (pintype "passive"))
    )
    (net (code "87") (name "Net-(U1-NC)") (class "Default")
      (node (ref "R187") (pin "2") (pinfunction "2_2") (pintype "passive"))
      (node (ref "U1") (pin "2") (pinfunction "NC_2") (pintype "passive"))
    )
    (net (code "88") (name "Net-(U1-OE{slash}NC)") (class "Default")
      (node (ref "R182") (pin "2") (pinfunction "2_2") (pintype "passive"))
      (node (ref "U1") (pin "1") (pinfunction "OE/NC_1") (pintype "passive"))
    )
    (net (code "89") (name "Net-(U1-VDD)") (class "Default")
      (node (ref "C56") (pin "1") (pinfunction "1_1") (pintype "passive"))
      (node (ref "C57") (pin "1") (pinfunction "1_1") (pintype "passive"))
      (node (ref "FB3") (pin "1") (pinfunction "1_1") (pintype "passive"))
      (node (ref "U1") (pin "6") (pinfunction "VDD_6") (pintype "passive"))
    )
    (net (code "90") (name "ORIN_DP_AUX_CH2_HPD") (class "Default")
      (node (ref "B1") (pin "K50") (pinfunction "DP2_HPD_K50") (pintype "bidirectional"))
    )
    (net (code "91") (name "ORIN_DP_CEC") (class "Default")
      (node (ref "B1") (pin "J50") (pinfunction "HDMI_CEC_J50") (pintype "bidirectional"))
    )
    (net (code "92") (name "ORIN_DP_SCL_AUX_P") (class "Default")
      (node (ref "B1") (pin "G53") (pinfunction "DP2_AUX_CH_P_G53") (pintype "bidirectional"))
    )
    (net (code "93") (name "ORIN_DP_SDA_AUX_N") (class "Default")
      (node (ref "B1") (pin "G54") (pinfunction "DP2_AUX_CH_N_G54") (pintype "bidirectional"))
    )
    (net (code "94") (name "ORIN_FORCE_SHUTDOWN") (class "Default")
      (node (ref "Q10") (pin "1") (pinfunction "B_1") (pintype "input"))
    )
    (net (code "95") (name "ORIN_HDMI_DP2_TXD0N") (class "Default")
      (node (ref "B1") (pin "D52") (pinfunction "HDMI_DP2_TX0_N_D52") (pintype "bidirectional"))
    )
    (net (code "96") (name "ORIN_HDMI_DP2_TXD0P") (class "Default")
      (node (ref "B1") (pin "D51") (pinfunction "HDMI_DP2_TX0_P_D51") (pintype "bidirectional"))
    )
    (net (code "97") (name "ORIN_HDMI_DP2_TXD1N") (class "Default")
      (node (ref "B1") (pin "B52") (pinfunction "HDMI_DP2_TX1_N_B52") (pintype "bidirectional"))
    )
    (net (code "98") (name "ORIN_HDMI_DP2_TXD1P") (class "Default")
      (node (ref "B1") (pin "B51") (pinfunction "HDMI_DP2_TX1_P_B51") (pintype "bidirectional"))
    )
    (net (code "99") (name "ORIN_HDMI_DP2_TXD2N") (class "Default")
      (node (ref "B1") (pin "A50") (pinfunction "HDMI_DP2_TX2_N_A50") (pintype "bidirectional"))
    )
    (net (code "100") (name "ORIN_HDMI_DP2_TXD2P") (class "Default")
      (node (ref "B1") (pin "A51") (pinfunction "HDMI_DP2_TX2_P_A51") (pintype "bidirectional"))
    )
    (net (code "101") (name "ORIN_HDMI_DP2_TXD3N") (class "Default")
      (node (ref "B1") (pin "C50") (pinfunction "HDMI_DP2_TX3_N_C50") (pintype "bidirectional"))
    )
    (net (code "102") (name "ORIN_HDMI_DP2_TXD3P") (class "Default")
      (node (ref "B1") (pin "C51") (pinfunction "HDMI_DP2_TX3_P_C51") (pintype "bidirectional"))
    )
    (net (code "103") (name "ORIN_PCIE1_CLK_N") (class "Default")
      (node (ref "B1") (pin "D48") (pinfunction "HDMI_DP1_TX2_N_D48") (pintype "bidirectional"))
    )
    (net (code "104") (name "ORIN_PCIE1_CLK_P") (class "Default")
      (node (ref "B1") (pin "D49") (pinfunction "HDMI_DP1_TX2_P_D49") (pintype "bidirectional"))
    )
    (net (code "105") (name "ORIN_PCIE_CLKREQ") (class "Default")
      (node (ref "B1") (pin "C8") (pinfunction "PEX_C5_CLKREQ_N_C8") (pintype "bidirectional"))
    )
    (net (code "106") (name "ORIN_PEX_CLK4_N") (class "Default")
      (node (ref "R155") (pin "2") (pinfunction "2_2") (pintype "passive"))
    )
    (net (code "107") (name "ORIN_PEX_CLK4_P") (class "Default")
      (node (ref "R157") (pin "2") (pinfunction "2_2") (pintype "passive"))
    )
    (net (code "108") (name "ORIN_PEX_CLK5_N") (class "Default")
      (node (ref "B1") (pin "F25") (pinfunction "PEX_CLK5_N_F25") (pintype "bidirectional"))
    )
    (net (code "109") (name "ORIN_PEX_CLK5_P") (class "Default")
      (node (ref "B1") (pin "F24") (pinfunction "PEX_CLK5_P_F24") (pintype "bidirectional"))
    )
    (net (code "110") (name "ORIN_PEX_L0_CLKREQ") (class "Default")
      (node (ref "B1") (pin "D9") (pinfunction "PEX_C1_CLKREQ_N_D9") (pintype "bidirectional"))
    )
    (net (code "111") (name "ORIN_PEX_L0_RST_N") (class "Default")
      (node (ref "B1") (pin "B9") (pinfunction "PEX_C1_RST_N_B9") (pintype "bidirectional"))
    )
    (net (code "112") (name "ORIN_PEX_L4_CLKREQ") (class "Default")
      (node (ref "B1") (pin "G8") (pinfunction "PEX_C4_CLKREQ_N_G8") (pintype "bidirectional"))
    )
    (net (code "113") (name "ORIN_PEX_L4_RST_N") (class "Default")
      (node (ref "B1") (pin "J9") (pinfunction "PEX_C4_RST_N_J9") (pintype "bidirectional"))
    )
    (net (code "114") (name "ORIN_PEX_L5_RST_N") (class "Default")
      (node (ref "B1") (pin "H10") (pinfunction "PEX_C5_RST_N_H10") (pintype "bidirectional"))
    )
    (net (code "115") (name "ORIN_SPI_1_RST_1") (class "Default")
      (node (ref "B1") (pin "A48") (pinfunction "HDMI_DP1_TX0_N_A48") (pintype "bidirectional"))
    )
    (net (code "116") (name "ORIN_SPI_1_nINT_1") (class "Default")
      (node (ref "B1") (pin "J52") (pinfunction "DP1_AUX_CH_P_J52") (pintype "bidirectional"))
      (node (ref "R133") (pin "1") (pinfunction "1_1") (pintype "passive"))
    )
    (net (code "117") (name "ORIN_SPI_3_nINT_1") (class "Default")
      (node (ref "B1") (pin "J53") (pinfunction "DP1_AUX_CH_N_J53") (pintype "bidirectional"))
      (node (ref "R132") (pin "1") (pinfunction "1_1") (pintype "passive"))
    )
    (net (code "118") (name "ORIN_UPHY_CLK1_N") (class "Default")
      (node (ref "B1") (pin "F17") (pinfunction "UPHY_REFCLK1_N_F17") (pintype "bidirectional"))
    )
    (net (code "119") (name "ORIN_UPHY_CLK1_P") (class "Default")
      (node (ref "B1") (pin "F16") (pinfunction "UPHY_REFCLK1_P_F16") (pintype "bidirectional"))
    )
    (net (code "120") (name "ORIN_UPHY_RXD0_N") (class "Default")
      (node (ref "B1") (pin "A23") (pinfunction "UPHY_RX0_N_A23") (pintype "bidirectional"))
    )
    (net (code "121") (name "ORIN_UPHY_RXD0_P") (class "Default")
      (node (ref "B1") (pin "A22") (pinfunction "UPHY_RX0_P_A22") (pintype "bidirectional"))
    )
    (net (code "122") (name "ORIN_UPHY_RXD1_N") (class "Default")
      (node (ref "B1") (pin "C22") (pinfunction "UPHY_RX1_N_C22") (pintype "bidirectional"))
    )
    (net (code "123") (name "ORIN_UPHY_RXD1_P") (class "Default")
      (node (ref "B1") (pin "C23") (pinfunction "UPHY_RX1_P_C23") (pintype "bidirectional"))
    )
    (net (code "124") (name "ORIN_UPHY_RXD6_N") (class "Default")
      (node (ref "B1") (pin "B17") (pinfunction "UPHY_RX6_N_B17") (pintype "bidirectional"))
    )
    (net (code "125") (name "ORIN_UPHY_RXD6_P") (class "Default")
      (node (ref "B1") (pin "B16") (pinfunction "UPHY_RX6_P_B16") (pintype "bidirectional"))
    )
    (net (code "126") (name "ORIN_UPHY_RXD7_N") (class "Default")
      (node (ref "B1") (pin "D17") (pinfunction "UPHY_RX7_N_D17") (pintype "bidirectional"))
    )
    (net (code "127") (name "ORIN_UPHY_RXD7_P") (class "Default")
      (node (ref "B1") (pin "D16") (pinfunction "UPHY_RX7_P_D16") (pintype "bidirectional"))
    )
    (net (code "128") (name "ORIN_UPHY_RXD8_N") (class "Default")
      (node (ref "B1") (pin "A14") (pinfunction "UPHY_RX8_N_A14") (pintype "bidirectional"))
    )
    (net (code "129") (name "ORIN_UPHY_RXD8_P") (class "Default")
      (node (ref "B1") (pin "A15") (pinfunction "UPHY_RX8_P_A15") (pintype "bidirectional"))
    )
    (net (code "130") (name "ORIN_UPHY_RXD9_N") (class "Default")
      (node (ref "B1") (pin "C14") (pinfunction "UPHY_RX9_N_C14") (pintype "bidirectional"))
    )
    (net (code "131") (name "ORIN_UPHY_RXD9_P") (class "Default")
      (node (ref "B1") (pin "C15") (pinfunction "UPHY_RX9_P_C15") (pintype "bidirectional"))
    )
    (net (code "132") (name "ORIN_UPHY_RXD10_N") (class "Default")
      (node (ref "B1") (pin "B13") (pinfunction "UPHY_RX10_N_B13") (pintype "bidirectional"))
    )
    (net (code "133") (name "ORIN_UPHY_RXD10_P") (class "Default")
      (node (ref "B1") (pin "B12") (pinfunction "UPHY_RX10_P_B12") (pintype "bidirectional"))
    )
    (net (code "134") (name "ORIN_UPHY_RXD11_N") (class "Default")
      (node (ref "B1") (pin "D13") (pinfunction "UPHY_RX11_N_D13") (pintype "bidirectional"))
    )
    (net (code "135") (name "ORIN_UPHY_RXD11_P") (class "Default")
      (node (ref "B1") (pin "D12") (pinfunction "UPHY_RX11_P_D12") (pintype "bidirectional"))
    )
    (net (code "136") (name "ORIN_UPHY_TXD0_N") (class "Default")
      (node (ref "B1") (pin "J23") (pinfunction "UPHY_TX0_N_J23") (pintype "bidirectional"))
    )
    (net (code "137") (name "ORIN_UPHY_TXD0_P") (class "Default")
      (node (ref "B1") (pin "J22") (pinfunction "UPHY_TX0_P_J22") (pintype "bidirectional"))
    )
    (net (code "138") (name "ORIN_UPHY_TXD1_N") (class "Default")
      (node (ref "B1") (pin "G22") (pinfunction "UPHY_TX1_N_G22") (pintype "bidirectional"))
    )
    (net (code "139") (name "ORIN_UPHY_TXD1_P") (class "Default")
      (node (ref "B1") (pin "G23") (pinfunction "UPHY_TX1_P_G23") (pintype "bidirectional"))
    )
    (net (code "140") (name "ORIN_UPHY_TXD6_N") (class "Default")
      (node (ref "C42") (pin "2") (pinfunction "2_2") (pintype "passive"))
    )
    (net (code "141") (name "ORIN_UPHY_TXD6_P") (class "Default")
      (node (ref "C43") (pin "2") (pinfunction "2_2") (pintype "passive"))
    )
    (net (code "142") (name "ORIN_UPHY_TXD7_N") (class "Default")
      (node (ref "C44") (pin "2") (pinfunction "2_2") (pintype "passive"))
    )
    (net (code "143") (name "ORIN_UPHY_TXD7_P") (class "Default")
      (node (ref "C45") (pin "2") (pinfunction "2_2") (pintype "passive"))
    )
    (net (code "144") (name "ORIN_UPHY_TXD8_N") (class "Default")
      (node (ref "B1") (pin "J15") (pinfunction "UPHY_TX8_N_J15") (pintype "bidirectional"))
    )
    (net (code "145") (name "ORIN_UPHY_TXD8_P") (class "Default")
      (node (ref "B1") (pin "J14") (pinfunction "UPHY_TX8_P_J14") (pintype "bidirectional"))
    )
    (net (code "146") (name "ORIN_UPHY_TXD9_N") (class "Default")
      (node (ref "B1") (pin "G14") (pinfunction "UPHY_TX9_N_G14") (pintype "bidirectional"))
    )
    (net (code "147") (name "ORIN_UPHY_TXD9_P") (class "Default")
      (node (ref "B1") (pin "G15") (pinfunction "UPHY_TX9_P_G15") (pintype "bidirectional"))
    )
    (net (code "148") (name "ORIN_UPHY_TXD10_N") (class "Default")
      (node (ref "B1") (pin "K12") (pinfunction "UPHY_TX10_N_K12") (pintype "bidirectional"))
    )
    (net (code "149") (name "ORIN_UPHY_TXD10_P") (class "Default")
      (node (ref "B1") (pin "K13") (pinfunction "UPHY_TX10_P_K13") (pintype "bidirectional"))
    )
    (net (code "150") (name "ORIN_UPHY_TXD11_N") (class "Default")
      (node (ref "B1") (pin "H13") (pinfunction "UPHY_TX11_N_H13") (pintype "bidirectional"))
    )
    (net (code "151") (name "ORIN_UPHY_TXD11_P") (class "Default")
      (node (ref "B1") (pin "H12") (pinfunction "UPHY_TX11_P_H12") (pintype "bidirectional"))
    )
    (net (code "152") (name "ORIN_USB0_DN") (class "Default")
      (node (ref "B1") (pin "F13") (pinfunction "USB0_N_F13") (pintype "bidirectional"))
    )
    (net (code "153") (name "ORIN_USB0_DP") (class "Default")
      (node (ref "B1") (pin "F12") (pinfunction "USB0_P_F12") (pintype "bidirectional"))
    )
    (net (code "154") (name "ORIN_USB1_DN") (class "Default")
      (node (ref "B1") (pin "C10") (pinfunction "USB1_N_C10") (pintype "bidirectional"))
    )
    (net (code "155") (name "ORIN_USB1_DP") (class "Default")
      (node (ref "B1") (pin "C11") (pinfunction "USB1_P_C11") (pintype "bidirectional"))
    )
    (net (code "156") (name "ORIN_USB2_DN") (class "Default")
      (node (ref "B1") (pin "A11") (pinfunction "USB2_N_A11") (pintype "bidirectional"))
    )
    (net (code "157") (name "ORIN_USB2_DP") (class "Default")
      (node (ref "B1") (pin "A10") (pinfunction "USB2_P_A10") (pintype "bidirectional"))
    )
    (net (code "158") (name "ORIN_USB3_DN") (class "Default")
      (node (ref "B1") (pin "G10") (pinfunction "USB3_N_G10") (pintype "bidirectional"))
    )
    (net (code "159") (name "ORIN_USB3_DP") (class "Default")
      (node (ref "B1") (pin "G11") (pinfunction "USB3_P_G11") (pintype "bidirectional"))
    )
    (net (code "161") (name "THERM_ALERT_N") (class "Default")
      (node (ref "B1") (pin "L56") (pinfunction "TEMP_ALERT_N_L56") (pintype "bidirectional"))
      (node (ref "R193") (pin "1") (pinfunction "1_1") (pintype "passive"))
    )
    (net (code "162") (name "VIN_PWR_BAD_N") (class "Default")
      (node (ref "B1") (pin "L55") (pinfunction "VDDIN_PWR_BAD_N_L55") (pintype "bidirectional"))
      (node (ref "R612") (pin "1") (pinfunction "1_1") (pintype "passive"))
      (node (ref "R613") (pin "1") (pinfunction "1_1") (pintype "passive"))
    )
    (net (code "163") (name "unconnected-(B1D-PEX_C0_CLKREQ_N-PadE11)") (class "Default")
      (node (ref "B1") (pin "E11") (pinfunction "PEX_C0_CLKREQ_N_E11") (pintype "bidirectional"))
    )
    (net (code "164") (name "unconnected-(B1D-PEX_C0_RST_N-PadD10)") (class "Default")
      (node (ref "B1") (pin "D10") (pinfunction "PEX_C0_RST_N_D10") (pintype "bidirectional"))
    )
    (net (code "165") (name "unconnected-(B1D-PEX_CLK0_N-PadE14)") (class "Default")
      (node (ref "B1") (pin "E14") (pinfunction "PEX_CLK0_N_E14") (pintype "bidirectional"))
    )
    (net (code "166") (name "unconnected-(B1D-PEX_CLK0_P-PadE15)") (class "Default")
      (node (ref "B1") (pin "E15") (pinfunction "PEX_CLK0_P_E15") (pintype "bidirectional"))
    )
    (net (code "167") (name "unconnected-(B1D-UPHY_REFCLK6_N-PadE26)") (class "Default")
      (node (ref "B1") (pin "E26") (pinfunction "UPHY_REFCLK6_N_E26") (pintype "bidirectional"))
    )
    (net (code "168") (name "unconnected-(B1D-UPHY_REFCLK6_P-PadE27)") (class "Default")
      (node (ref "B1") (pin "E27") (pinfunction "UPHY_REFCLK6_P_E27") (pintype "bidirectional"))
    )
    (net (code "169") (name "unconnected-(R165-Pad1)") (class "Default")
      (node (ref "R165") (pin "1") (pinfunction "1_1") (pintype "passive"))
    )
  )
)
